# controller.net
KiCad netlist of a schematic drawn in EAGLE
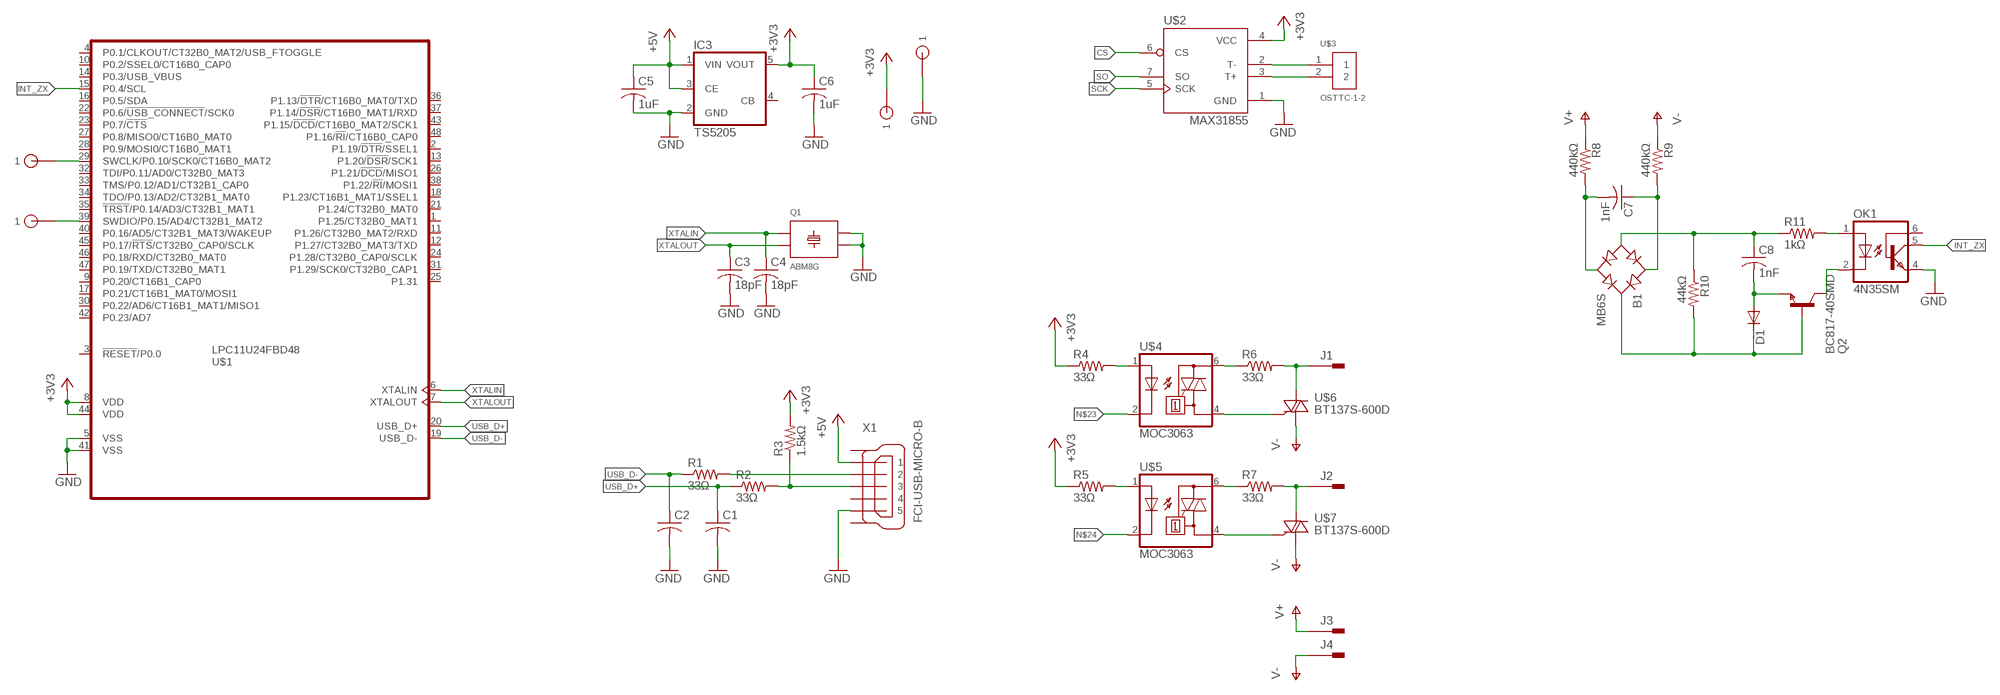
[diagram p0: schematic, sheet 1]

(export (version "E")
  (design (tool "Eeschema 10.0.6"))
  (components
    (comp (ref "B1")
      (value "MB6S")
      (footprint "eagle-import:SOIC-4")
      (libsource (lib "eagle-import") (part "MBS6"))
    )
    (comp (ref "C1")
      (value "C-USC0402")
      (footprint "eagle-import:C0402")
      (libsource (lib "eagle-import") (part "C-USC0402"))
    )
    (comp (ref "C2")
      (value "C-USC0402")
      (footprint "eagle-import:C0402")
      (libsource (lib "eagle-import") (part "C-USC0402"))
    )
    (comp (ref "C3")
      (value "18pF")
      (footprint "eagle-import:C0402K")
      (libsource (lib "eagle-import") (part "C-USC0402K"))
    )
    (comp (ref "C4")
      (value "18pF")
      (footprint "eagle-import:C0402K")
      (libsource (lib "eagle-import") (part "C-USC0402K"))
    )
    (comp (ref "C5")
      (value "1uF")
      (footprint "eagle-import:C0402K")
      (libsource (lib "eagle-import") (part "C-USC0402K"))
    )
    (comp (ref "C6")
      (value "1uF")
      (footprint "eagle-import:C0402K")
      (libsource (lib "eagle-import") (part "C-USC0402K"))
    )
    (comp (ref "C7")
      (value "1nF")
      (footprint "eagle-import:C0402K")
      (libsource (lib "eagle-import") (part "C-USC0402K"))
    )
    (comp (ref "C8")
      (value "1nF")
      (footprint "eagle-import:C0402K")
      (libsource (lib "eagle-import") (part "C-USC0402K"))
    )
    (comp (ref "D1")
      (value "DIODE-SOD80C")
      (footprint "eagle-import:SOD80C")
      (libsource (lib "eagle-import") (part "DIODE-SOD80C"))
    )
    (comp (ref "IC3")
      (value "TS5205")
      (footprint "eagle-import:SOT25")
      (libsource (lib "eagle-import") (part "TS5205"))
    )
    (comp (ref "J1")
      (value "PIN2F061.100")
      (footprint "eagle-import:F061.100")
      (libsource (lib "eagle-import") (part "PIN2F061.100"))
    )
    (comp (ref "J2")
      (value "PIN2F061.100")
      (footprint "eagle-import:F061.100")
      (libsource (lib "eagle-import") (part "PIN2F061.100"))
    )
    (comp (ref "J3")
      (value "PIN2F061.100")
      (footprint "eagle-import:F061.100")
      (libsource (lib "eagle-import") (part "PIN2F061.100"))
    )
    (comp (ref "J4")
      (value "PIN2F061.100")
      (footprint "eagle-import:F061.100")
      (libsource (lib "eagle-import") (part "PIN2F061.100"))
    )
    (comp (ref "OK1")
      (value "4N35SM")
      (footprint "eagle-import:DIL6-SMD")
      (fields (field (name "MF") "FAIRCHILD SEMICONDUCTOR") (field (name "MPN") "4N35S-M"))
      (libsource (lib "eagle-import") (part "4N?MS35"))
    )
    (comp (ref "Q1")
      (value "ABM8G")
      (footprint "eagle-import:SMD-4")
      (libsource (lib "eagle-import") (part "ABM8G"))
    )
    (comp (ref "Q2")
      (value "BC817-40SMD")
      (footprint "eagle-import:SOT23-BEC")
      (libsource (lib "eagle-import") (part "BC817SMD-40"))
    )
    (comp (ref "R1")
      (value "33Ω")
      (footprint "eagle-import:R0402")
      (libsource (lib "eagle-import") (part "R-US_R0402"))
    )
    (comp (ref "R2")
      (value "33Ω")
      (footprint "eagle-import:R0402")
      (libsource (lib "eagle-import") (part "R-US_R0402"))
    )
    (comp (ref "R3")
      (value "1.5kΩ")
      (footprint "eagle-import:R0402")
      (libsource (lib "eagle-import") (part "R-US_R0402"))
    )
    (comp (ref "R4")
      (value "33Ω")
      (footprint "eagle-import:R0402")
      (libsource (lib "eagle-import") (part "R-US_R0402"))
    )
    (comp (ref "R5")
      (value "33Ω")
      (footprint "eagle-import:R0402")
      (libsource (lib "eagle-import") (part "R-US_R0402"))
    )
    (comp (ref "R6")
      (value "33Ω")
      (footprint "eagle-import:R0402")
      (libsource (lib "eagle-import") (part "R-US_R0402"))
    )
    (comp (ref "R7")
      (value "33Ω")
      (footprint "eagle-import:R0402")
      (libsource (lib "eagle-import") (part "R-US_R0402"))
    )
    (comp (ref "R8")
      (value "440kΩ")
      (footprint "eagle-import:R0402")
      (libsource (lib "eagle-import") (part "R-US_R0402"))
    )
    (comp (ref "R9")
      (value "440kΩ")
      (footprint "eagle-import:R0402")
      (libsource (lib "eagle-import") (part "R-US_R0402"))
    )
    (comp (ref "R10")
      (value "44kΩ")
      (footprint "eagle-import:R0402")
      (libsource (lib "eagle-import") (part "R-US_R0402"))
    )
    (comp (ref "R11")
      (value "1kΩ")
      (footprint "eagle-import:R0402")
      (libsource (lib "eagle-import") (part "R-US_R0402"))
    )
    (comp (ref "TP1")
      (value "TESTPOINT")
      (footprint "eagle-import:TESTPOINT-SMD")
      (libsource (lib "eagle-import") (part "TESTPOINT"))
    )
    (comp (ref "TP2")
      (value "TESTPOINT")
      (footprint "eagle-import:TESTPOINT-SMD")
      (libsource (lib "eagle-import") (part "TESTPOINT"))
    )
    (comp (ref "TP6")
      (value "TESTPOINT")
      (footprint "eagle-import:TESTPOINT-SMD")
      (libsource (lib "eagle-import") (part "TESTPOINT"))
    )
    (comp (ref "TP7")
      (value "TESTPOINT")
      (footprint "eagle-import:TESTPOINT-SMD")
      (libsource (lib "eagle-import") (part "TESTPOINT"))
    )
    (comp (ref "U$1")
      (value "LPC11U24FBD48")
      (footprint "eagle-import:LQFP48")
      (libsource (lib "eagle-import") (part "LPC11U24FBD48"))
    )
    (comp (ref "U$2")
      (value "MAX31855")
      (footprint "eagle-import:SO08")
      (libsource (lib "eagle-import") (part "MAX31855"))
    )
    (comp (ref "U$3")
      (value "OSTTC-1-2")
      (footprint "eagle-import:OSTTC-1-2")
      (libsource (lib "eagle-import") (part "OSTTC-1-2"))
    )
    (comp (ref "U$4")
      (value "MOC3063")
      (footprint "eagle-import:SMD6")
      (libsource (lib "eagle-import") (part "MOC3063"))
    )
    (comp (ref "U$5")
      (value "MOC3063")
      (footprint "eagle-import:SMD6")
      (libsource (lib "eagle-import") (part "MOC3063"))
    )
    (comp (ref "U$6")
      (value "BT137S-600D")
      (footprint "eagle-import:TO-252")
      (libsource (lib "eagle-import") (part "BT137S-600D"))
    )
    (comp (ref "U$7")
      (value "BT137S-600D")
      (footprint "eagle-import:TO-252")
      (libsource (lib "eagle-import") (part "BT137S-600D"))
    )
    (comp (ref "X1")
      (value "FCI-USB-MICRO-B")
      (footprint "eagle-import:FCI-MICRO-USB-B")
      (libsource (lib "eagle-import") (part "FCI-USB-MICRO-B"))
    )
  )
  (nets
    (net (code "1") (name "+3V3") (class "Default")
      (node (ref "C6") (pin "1") (pinfunction "1_1") (pintype "passive"))
      (node (ref "IC3") (pin "5") (pinfunction "VOUT_5") (pintype "passive"))
      (node (ref "R3") (pin "2") (pinfunction "2_2") (pintype "passive"))
      (node (ref "R4") (pin "1") (pinfunction "1_1") (pintype "passive"))
      (node (ref "R5") (pin "1") (pinfunction "1_1") (pintype "passive"))
      (node (ref "TP6") (pin "1") (pinfunction "1_1") (pintype "passive"))
      (node (ref "U$1") (pin "44") (pinfunction "VDD_44") (pintype "bidirectional"))
      (node (ref "U$1") (pin "8") (pinfunction "VDD_8") (pintype "bidirectional"))
      (node (ref "U$2") (pin "4") (pinfunction "VCC_4") (pintype "power_in"))
    )
    (net (code "2") (name "+5V") (class "Default")
      (node (ref "C5") (pin "1") (pinfunction "1_1") (pintype "passive"))
      (node (ref "IC3") (pin "1") (pinfunction "VIN_1") (pintype "input"))
      (node (ref "IC3") (pin "3") (pinfunction "CE_3") (pintype "input"))
      (node (ref "X1") (pin "1") (pinfunction "1_1") (pintype "passive"))
    )
    (net (code "3") (name "/G1") (class "Default")
      (node (ref "X1") (pin "M1") (pinfunction "G1_M1") (pintype "power_in"))
    )
    (net (code "4") (name "/G2") (class "Default")
      (node (ref "X1") (pin "M2") (pinfunction "G2_M2") (pintype "power_in"))
    )
    (net (code "5") (name "CS") (class "Default")
      (node (ref "U$2") (pin "6") (pinfunction "CS_6") (pintype "input"))
    )
    (net (code "6") (name "GND") (class "Default")
      (node (ref "C1") (pin "2") (pinfunction "2_2") (pintype "passive"))
      (node (ref "C2") (pin "2") (pinfunction "2_2") (pintype "passive"))
      (node (ref "C3") (pin "2") (pinfunction "2_2") (pintype "passive"))
      (node (ref "C4") (pin "2") (pinfunction "2_2") (pintype "passive"))
      (node (ref "C5") (pin "2") (pinfunction "2_2") (pintype "passive"))
      (node (ref "C6") (pin "2") (pinfunction "2_2") (pintype "passive"))
      (node (ref "IC3") (pin "2") (pinfunction "GND_2") (pintype "passive"))
      (node (ref "OK1") (pin "4") (pinfunction "EMI_4") (pintype "passive"))
      (node (ref "Q1") (pin "2") (pinfunction "GND1_2") (pintype "power_in"))
      (node (ref "Q1") (pin "4") (pinfunction "GND2_4") (pintype "power_in"))
      (node (ref "TP7") (pin "1") (pinfunction "1_1") (pintype "passive"))
      (node (ref "U$1") (pin "41") (pinfunction "VSS_41") (pintype "bidirectional"))
      (node (ref "U$1") (pin "5") (pinfunction "VSS_5") (pintype "bidirectional"))
      (node (ref "U$2") (pin "1") (pinfunction "GND_1") (pintype "power_in"))
      (node (ref "X1") (pin "5") (pinfunction "5_5") (pintype "passive"))
    )
    (net (code "7") (name "INT_ZX") (class "Default")
      (node (ref "OK1") (pin "5") (pinfunction "COL_5") (pintype "passive"))
      (node (ref "U$1") (pin "15") (pinfunction "P0.4/SCL_15") (pintype "bidirectional"))
    )
    (net (code "8") (name "N$23") (class "Default")
      (node (ref "U$4") (pin "2") (pinfunction "C_2") (pintype "passive"))
    )
    (net (code "9") (name "N$24") (class "Default")
      (node (ref "U$5") (pin "2") (pinfunction "C_2") (pintype "passive"))
    )
    (net (code "10") (name "Net-(B1-AC1)") (class "Default")
      (node (ref "B1") (pin "~1") (pinfunction "AC1_~1") (pintype "passive"))
      (node (ref "C7") (pin "1") (pinfunction "1_1") (pintype "passive"))
      (node (ref "R9") (pin "2") (pinfunction "2_2") (pintype "passive"))
    )
    (net (code "11") (name "Net-(B1-AC2)") (class "Default")
      (node (ref "B1") (pin "~2") (pinfunction "AC2_~2") (pintype "passive"))
      (node (ref "C7") (pin "2") (pinfunction "2_2") (pintype "passive"))
      (node (ref "R8") (pin "2") (pinfunction "2_2") (pintype "passive"))
    )
    (net (code "12") (name "Net-(B1-Pad+)") (class "Default")
      (node (ref "B1") (pin "+") (pinfunction "+_+") (pintype "passive"))
      (node (ref "D1") (pin "C") (pinfunction "C_C") (pintype "passive"))
      (node (ref "Q2") (pin "B") (pinfunction "B_B") (pintype "passive"))
      (node (ref "R10") (pin "2") (pinfunction "2_2") (pintype "passive"))
    )
    (net (code "13") (name "Net-(B1-Pad-)") (class "Default")
      (node (ref "B1") (pin "-") (pinfunction "-_-") (pintype "passive"))
      (node (ref "C8") (pin "1") (pinfunction "1_1") (pintype "passive"))
      (node (ref "R10") (pin "1") (pinfunction "1_1") (pintype "passive"))
      (node (ref "R11") (pin "1") (pinfunction "1_1") (pintype "passive"))
    )
    (net (code "14") (name "Net-(C8-Pad2)") (class "Default")
      (node (ref "C8") (pin "2") (pinfunction "2_2") (pintype "passive"))
      (node (ref "D1") (pin "A") (pinfunction "A_A") (pintype "passive"))
      (node (ref "Q2") (pin "E") (pinfunction "E_E") (pintype "passive"))
    )
    (net (code "15") (name "Net-(OK1-A)") (class "Default")
      (node (ref "OK1") (pin "1") (pinfunction "A_1") (pintype "passive"))
      (node (ref "R11") (pin "2") (pinfunction "2_2") (pintype "passive"))
    )
    (net (code "16") (name "Net-(OK1-C)") (class "Default")
      (node (ref "OK1") (pin "2") (pinfunction "C_2") (pintype "passive"))
      (node (ref "Q2") (pin "C") (pinfunction "C_C") (pintype "passive"))
    )
    (net (code "17") (name "Net-(R1-Pad2)") (class "Default")
      (node (ref "R1") (pin "2") (pinfunction "2_2") (pintype "passive"))
      (node (ref "X1") (pin "2") (pinfunction "2_2") (pintype "passive"))
    )
    (net (code "18") (name "Net-(R2-Pad2)") (class "Default")
      (node (ref "R2") (pin "2") (pinfunction "2_2") (pintype "passive"))
      (node (ref "R3") (pin "1") (pinfunction "1_1") (pintype "passive"))
      (node (ref "X1") (pin "3") (pinfunction "3_3") (pintype "passive"))
    )
    (net (code "19") (name "Net-(U$1-SWCLK{slash}P0.10{slash}SCK0{slash}CT16B0_MAT2)") (class "Default")
      (node (ref "TP2") (pin "1") (pinfunction "1_1") (pintype "passive"))
      (node (ref "U$1") (pin "29") (pinfunction "SWCLK/P0.10/SCK0/CT16B0_MAT2_29") (pintype "bidirectional"))
    )
    (net (code "20") (name "Net-(U$1-SWDIO{slash}P0.15{slash}AD4{slash}CT32B1_MAT2)") (class "Default")
      (node (ref "TP1") (pin "1") (pinfunction "1_1") (pintype "passive"))
      (node (ref "U$1") (pin "39") (pinfunction "SWDIO/P0.15/AD4/CT32B1_MAT2_39") (pintype "bidirectional"))
    )
    (net (code "21") (name "Net-(U$2-T+)") (class "Default")
      (node (ref "U$2") (pin "3") (pinfunction "T+_3") (pintype "input"))
      (node (ref "U$3") (pin "2") (pinfunction "2_2") (pintype "passive"))
    )
    (net (code "22") (name "Net-(U$2-T-)") (class "Default")
      (node (ref "U$2") (pin "2") (pinfunction "T-_2") (pintype "input"))
      (node (ref "U$3") (pin "1") (pinfunction "1_1") (pintype "passive"))
    )
    (net (code "23") (name "Net-(U$4-A)") (class "Default")
      (node (ref "R4") (pin "2") (pinfunction "2_2") (pintype "passive"))
      (node (ref "U$4") (pin "1") (pinfunction "A_1") (pintype "passive"))
    )
    (net (code "24") (name "Net-(U$4-A1)") (class "Default")
      (node (ref "U$4") (pin "4") (pinfunction "A1_4") (pintype "passive"))
      (node (ref "U$6") (pin "2") (pinfunction "G_2") (pintype "passive"))
    )
    (net (code "25") (name "Net-(U$4-A2)") (class "Default")
      (node (ref "R6") (pin "1") (pinfunction "1_1") (pintype "passive"))
      (node (ref "U$4") (pin "6") (pinfunction "A2_6") (pintype "passive"))
    )
    (net (code "26") (name "Net-(U$5-A)") (class "Default")
      (node (ref "R5") (pin "2") (pinfunction "2_2") (pintype "passive"))
      (node (ref "U$5") (pin "1") (pinfunction "A_1") (pintype "passive"))
    )
    (net (code "27") (name "Net-(U$5-A1)") (class "Default")
      (node (ref "U$5") (pin "4") (pinfunction "A1_4") (pintype "passive"))
      (node (ref "U$7") (pin "2") (pinfunction "G_2") (pintype "passive"))
    )
    (net (code "28") (name "Net-(U$5-A2)") (class "Default")
      (node (ref "R7") (pin "1") (pinfunction "1_1") (pintype "passive"))
      (node (ref "U$5") (pin "6") (pinfunction "A2_6") (pintype "passive"))
    )
    (net (code "29") (name "Net-(U$6-A2)") (class "Default")
      (node (ref "J1") (pin "A1") (pinfunction "1_A1") (pintype "passive"))
      (node (ref "J1") (pin "A2") (pinfunction "1_A2") (pintype "passive"))
      (node (ref "R6") (pin "2") (pinfunction "2_2") (pintype "passive"))
      (node (ref "U$6") (pin "1") (pinfunction "A2_1") (pintype "passive"))
    )
    (net (code "30") (name "Net-(U$7-A2)") (class "Default")
      (node (ref "J2") (pin "A1") (pinfunction "1_A1") (pintype "passive"))
      (node (ref "J2") (pin "A2") (pinfunction "1_A2") (pintype "passive"))
      (node (ref "R7") (pin "2") (pinfunction "2_2") (pintype "passive"))
      (node (ref "U$7") (pin "1") (pinfunction "A2_1") (pintype "passive"))
    )
    (net (code "31") (name "SCK") (class "Default")
      (node (ref "U$2") (pin "5") (pinfunction "SCK_5") (pintype "input"))
    )
    (net (code "32") (name "SO") (class "Default")
      (node (ref "U$2") (pin "7") (pinfunction "SO_7") (pintype "output"))
    )
    (net (code "33") (name "USB_D+") (class "Default")
      (node (ref "C1") (pin "1") (pinfunction "1_1") (pintype "passive"))
      (node (ref "R2") (pin "1") (pinfunction "1_1") (pintype "passive"))
      (node (ref "U$1") (pin "20") (pinfunction "USB_D+_20") (pintype "bidirectional"))
    )
    (net (code "34") (name "USB_D-") (class "Default")
      (node (ref "C2") (pin "1") (pinfunction "1_1") (pintype "passive"))
      (node (ref "R1") (pin "1") (pinfunction "1_1") (pintype "passive"))
      (node (ref "U$1") (pin "19") (pinfunction "USB_D-_19") (pintype "bidirectional"))
    )
    (net (code "35") (name "V+") (class "Default")
      (node (ref "J3") (pin "A1") (pinfunction "1_A1") (pintype "passive"))
      (node (ref "J3") (pin "A2") (pinfunction "1_A2") (pintype "passive"))
      (node (ref "R8") (pin "1") (pinfunction "1_1") (pintype "passive"))
    )
    (net (code "36") (name "V-") (class "Default")
      (node (ref "J4") (pin "A1") (pinfunction "1_A1") (pintype "passive"))
      (node (ref "J4") (pin "A2") (pinfunction "1_A2") (pintype "passive"))
      (node (ref "R9") (pin "1") (pinfunction "1_1") (pintype "passive"))
      (node (ref "U$6") (pin "3") (pinfunction "A1_3") (pintype "passive"))
      (node (ref "U$7") (pin "3") (pinfunction "A1_3") (pintype "passive"))
    )
    (net (code "37") (name "XTALIN") (class "Default")
      (node (ref "C4") (pin "1") (pinfunction "1_1") (pintype "passive"))
      (node (ref "Q1") (pin "1") (pinfunction "1_1") (pintype "passive"))
      (node (ref "U$1") (pin "6") (pinfunction "XTALIN_6") (pintype "bidirectional"))
    )
    (net (code "38") (name "XTALOUT") (class "Default")
      (node (ref "C3") (pin "1") (pinfunction "1_1") (pintype "passive"))
      (node (ref "Q1") (pin "3") (pinfunction "2_3") (pintype "passive"))
      (node (ref "U$1") (pin "7") (pinfunction "XTALOUT_7") (pintype "bidirectional"))
    )
    (net (code "39") (name "unconnected-(IC3-CB-Pad4)") (class "Default")
      (node (ref "IC3") (pin "4") (pinfunction "CB_4") (pintype "input"))
    )
    (net (code "40") (name "unconnected-(OK1-BAS-Pad6)") (class "Default")
      (node (ref "OK1") (pin "6") (pinfunction "BAS_6") (pintype "passive"))
    )
    (net (code "41") (name "unconnected-(U$1-P0.1{slash}CLKOUT{slash}CT32B0_MAT2{slash}USB_FTOGGLE-Pad4)") (class "Default")
      (node (ref "U$1") (pin "4") (pinfunction "P0.1/CLKOUT/CT32B0_MAT2/USB_FTOGGLE_4") (pintype "bidirectional"))
    )
    (net (code "42") (name "unconnected-(U$1-P0.2{slash}SSEL0{slash}CT16B0_CAP0-Pad10)") (class "Default")
      (node (ref "U$1") (pin "10") (pinfunction "P0.2/SSEL0/CT16B0_CAP0_10") (pintype "bidirectional"))
    )
    (net (code "43") (name "unconnected-(U$1-P0.3{slash}USB_VBUS-Pad14)") (class "Default")
      (node (ref "U$1") (pin "14") (pinfunction "P0.3/USB_VBUS_14") (pintype "bidirectional"))
    )
    (net (code "44") (name "unconnected-(U$1-P0.5{slash}SDA-Pad16)") (class "Default")
      (node (ref "U$1") (pin "16") (pinfunction "P0.5/SDA_16") (pintype "bidirectional"))
    )
    (net (code "45") (name "unconnected-(U$1-P0.6{slash}~{USB_CONNECT}{slash}SCK0-Pad22)") (class "Default")
      (node (ref "U$1") (pin "22") (pinfunction "P0.6/~{USB_CONNECT}/SCK0_22") (pintype "bidirectional"))
    )
    (net (code "46") (name "unconnected-(U$1-P0.7{slash}~{CTS}-Pad23)") (class "Default")
      (node (ref "U$1") (pin "23") (pinfunction "P0.7/~{CTS}_23") (pintype "bidirectional"))
    )
    (net (code "47") (name "unconnected-(U$1-P0.8{slash}MISO0{slash}CT16B0_MAT0-Pad27)") (class "Default")
      (node (ref "U$1") (pin "27") (pinfunction "P0.8/MISO0/CT16B0_MAT0_27") (pintype "bidirectional"))
    )
    (net (code "48") (name "unconnected-(U$1-P0.9{slash}MOSI0{slash}CT16B0_MAT1-Pad28)") (class "Default")
      (node (ref "U$1") (pin "28") (pinfunction "P0.9/MOSI0/CT16B0_MAT1_28") (pintype "bidirectional"))
    )
    (net (code "49") (name "unconnected-(U$1-P0.16{slash}AD5{slash}CT32B1_MAT3{slash}WAKEUP-Pad40)") (class "Default")
      (node (ref "U$1") (pin "40") (pinfunction "P0.16/AD5/CT32B1_MAT3/WAKEUP_40") (pintype "bidirectional"))
    )
    (net (code "50") (name "unconnected-(U$1-P0.17{slash}~{RTS}{slash}CT32B0_CAP0{slash}SCLK-Pad45)") (class "Default")
      (node (ref "U$1") (pin "45") (pinfunction "P0.17/~{RTS}/CT32B0_CAP0/SCLK_45") (pintype "bidirectional"))
    )
    (net (code "51") (name "unconnected-(U$1-P0.18{slash}RXD{slash}CT32B0_MAT0-Pad46)") (class "Default")
      (node (ref "U$1") (pin "46") (pinfunction "P0.18/RXD/CT32B0_MAT0_46") (pintype "bidirectional"))
    )
    (net (code "52") (name "unconnected-(U$1-P0.19{slash}TXD{slash}CT32B0_MAT1-Pad47)") (class "Default")
      (node (ref "U$1") (pin "47") (pinfunction "P0.19/TXD/CT32B0_MAT1_47") (pintype "bidirectional"))
    )
    (net (code "53") (name "unconnected-(U$1-P0.20{slash}CT16B1_CAP0-Pad9)") (class "Default")
      (node (ref "U$1") (pin "9") (pinfunction "P0.20/CT16B1_CAP0_9") (pintype "bidirectional"))
    )
    (net (code "54") (name "unconnected-(U$1-P0.21{slash}CT16B1_MAT0{slash}MOSI1-Pad17)") (class "Default")
      (node (ref "U$1") (pin "17") (pinfunction "P0.21/CT16B1_MAT0/MOSI1_17") (pintype "bidirectional"))
    )
    (net (code "55") (name "unconnected-(U$1-P0.22{slash}AD6{slash}CT16B1_MAT1{slash}MISO1-Pad30)") (class "Default")
      (node (ref "U$1") (pin "30") (pinfunction "P0.22/AD6/CT16B1_MAT1/MISO1_30") (pintype "bidirectional"))
    )
    (net (code "56") (name "unconnected-(U$1-P0.23{slash}AD7-Pad42)") (class "Default")
      (node (ref "U$1") (pin "42") (pinfunction "P0.23/AD7_42") (pintype "bidirectional"))
    )
    (net (code "57") (name "unconnected-(U$1-P1.13{slash}~{DTR}{slash}CT16B0_MAT0{slash}TXD-Pad36)") (class "Default")
      (node (ref "U$1") (pin "36") (pinfunction "P1.13/~{DTR}/CT16B0_MAT0/TXD_36") (pintype "bidirectional"))
    )
    (net (code "58") (name "unconnected-(U$1-P1.14{slash}~{DSR}{slash}CT16B0_MAT1{slash}RXD-Pad37)") (class "Default")
      (node (ref "U$1") (pin "37") (pinfunction "P1.14/~{DSR}/CT16B0_MAT1/RXD_37") (pintype "bidirectional"))
    )
    (net (code "59") (name "unconnected-(U$1-P1.15{slash}~{DCD}{slash}CT16B0_MAT2{slash}SCK1-Pad43)") (class "Default")
      (node (ref "U$1") (pin "43") (pinfunction "P1.15/~{DCD}/CT16B0_MAT2/SCK1_43") (pintype "bidirectional"))
    )
    (net (code "60") (name "unconnected-(U$1-P1.16{slash}~{RI}{slash}CT16B0_CAP0-Pad48)") (class "Default")
      (node (ref "U$1") (pin "48") (pinfunction "P1.16/~{RI}/CT16B0_CAP0_48") (pintype "bidirectional"))
    )
    (net (code "61") (name "unconnected-(U$1-P1.19{slash}~{DTR}{slash}SSEL1-Pad2)") (class "Default")
      (node (ref "U$1") (pin "2") (pinfunction "P1.19/~{DTR}/SSEL1_2") (pintype "bidirectional"))
    )
    (net (code "62") (name "unconnected-(U$1-P1.20{slash}~{DSR}{slash}SCK1-Pad13)") (class "Default")
      (node (ref "U$1") (pin "13") (pinfunction "P1.20/~{DSR}/SCK1_13") (pintype "bidirectional"))
    )
    (net (code "63") (name "unconnected-(U$1-P1.21{slash}~{DCD}{slash}MISO1-Pad26)") (class "Default")
      (node (ref "U$1") (pin "26") (pinfunction "P1.21/~{DCD}/MISO1_26") (pintype "bidirectional"))
    )
    (net (code "64") (name "unconnected-(U$1-P1.22{slash}~{RI}{slash}MOSI1-Pad38)") (class "Default")
      (node (ref "U$1") (pin "38") (pinfunction "P1.22/~{RI}/MOSI1_38") (pintype "bidirectional"))
    )
    (net (code "65") (name "unconnected-(U$1-P1.23{slash}CT16B1_MAT1{slash}SSEL1-Pad18)") (class "Default")
      (node (ref "U$1") (pin "18") (pinfunction "P1.23/CT16B1_MAT1/SSEL1_18") (pintype "bidirectional"))
    )
    (net (code "66") (name "unconnected-(U$1-P1.24{slash}CT32B0_MAT0-Pad21)") (class "Default")
      (node (ref "U$1") (pin "21") (pinfunction "P1.24/CT32B0_MAT0_21") (pintype "bidirectional"))
    )
    (net (code "67") (name "unconnected-(U$1-P1.25{slash}CT32B0_MAT1-Pad1)") (class "Default")
      (node (ref "U$1") (pin "1") (pinfunction "P1.25/CT32B0_MAT1_1") (pintype "bidirectional"))
    )
    (net (code "68") (name "unconnected-(U$1-P1.26{slash}CT32B0_MAT2{slash}RXD-Pad11)") (class "Default")
      (node (ref "U$1") (pin "11") (pinfunction "P1.26/CT32B0_MAT2/RXD_11") (pintype "bidirectional"))
    )
    (net (code "69") (name "unconnected-(U$1-P1.27{slash}CT32B0_MAT3{slash}TXD-Pad12)") (class "Default")
      (node (ref "U$1") (pin "12") (pinfunction "P1.27/CT32B0_MAT3/TXD_12") (pintype "bidirectional"))
    )
    (net (code "70") (name "unconnected-(U$1-P1.28{slash}CT32B0_CAP0{slash}SCLK-Pad24)") (class "Default")
      (node (ref "U$1") (pin "24") (pinfunction "P1.28/CT32B0_CAP0/SCLK_24") (pintype "bidirectional"))
    )
    (net (code "71") (name "unconnected-(U$1-P1.29{slash}SCK0{slash}CT32B0_CAP1-Pad31)") (class "Default")
      (node (ref "U$1") (pin "31") (pinfunction "P1.29/SCK0/CT32B0_CAP1_31") (pintype "bidirectional"))
    )
    (net (code "72") (name "unconnected-(U$1-P1.31-Pad25)") (class "Default")
      (node (ref "U$1") (pin "25") (pinfunction "P1.31_25") (pintype "bidirectional"))
    )
    (net (code "73") (name "unconnected-(U$1-TDI{slash}P0.11{slash}AD0{slash}CT32B0_MAT3-Pad32)") (class "Default")
      (node (ref "U$1") (pin "32") (pinfunction "TDI/P0.11/AD0/CT32B0_MAT3_32") (pintype "bidirectional"))
    )
    (net (code "74") (name "unconnected-(U$1-TDO{slash}P0.13{slash}AD2{slash}CT32B1_MAT0-Pad34)") (class "Default")
      (node (ref "U$1") (pin "34") (pinfunction "TDO/P0.13/AD2/CT32B1_MAT0_34") (pintype "bidirectional"))
    )
    (net (code "75") (name "unconnected-(U$1-TMS{slash}P0.12{slash}AD1{slash}CT32B1_CAP0-Pad33)") (class "Default")
      (node (ref "U$1") (pin "33") (pinfunction "TMS/P0.12/AD1/CT32B1_CAP0_33") (pintype "bidirectional"))
    )
    (net (code "76") (name "unconnected-(U$1-~{RESET}{slash}P0.0-Pad3)") (class "Default")
      (node (ref "U$1") (pin "3") (pinfunction "~{RESET}/P0.0_3") (pintype "bidirectional"))
    )
    (net (code "77") (name "unconnected-(U$1-~{TRST}{slash}P0.14{slash}AD3{slash}CT32B1_MAT1-Pad35)") (class "Default")
      (node (ref "U$1") (pin "35") (pinfunction "~{TRST}/P0.14/AD3/CT32B1_MAT1_35") (pintype "bidirectional"))
    )
    (net (code "78") (name "unconnected-(X1-Pad4)") (class "Default")
      (node (ref "X1") (pin "4") (pinfunction "4_4") (pintype "passive"))
    )
  )
)
